# SPort_SBUS.net
KiCad netlist of a schematic drawn in Altium Designer
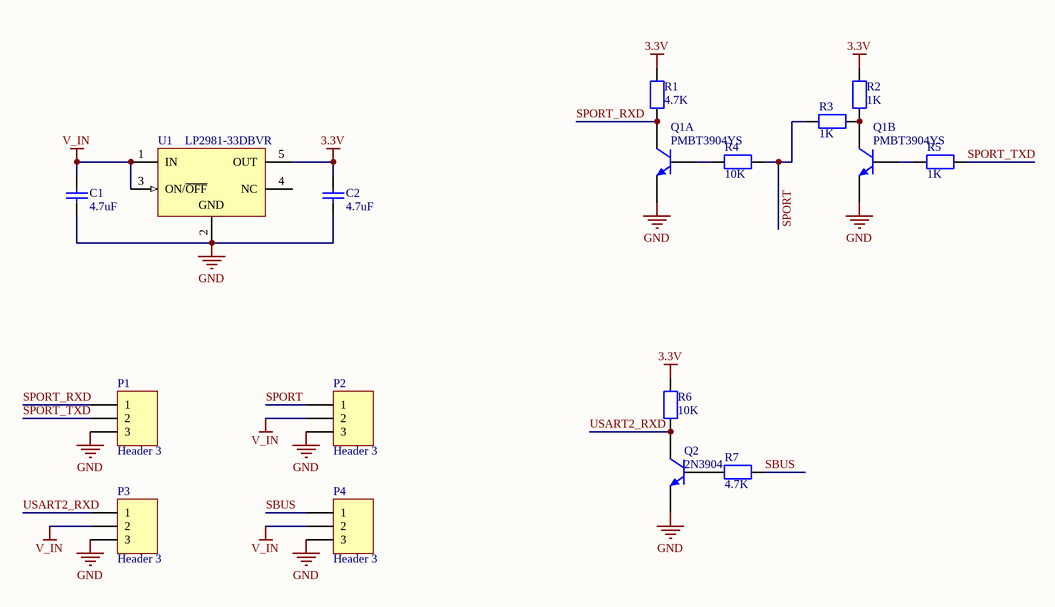
[diagram p0: SPort_SBUS.SchDoc]

(export (version "E")
  (design (tool "Eeschema 10.0.6"))
  (components
    (comp (ref "C1")
      (value "4.7uF")
      (footprint "0603_CAP")
      (fields (field (name "Comment") "Capacitor"))
      (libsource (lib "Passive_comp") (part "Capacitor"))
    )
    (comp (ref "C2")
      (value "4.7uF")
      (footprint "0603_CAP")
      (fields (field (name "Comment") "Capacitor"))
      (libsource (lib "Passive_comp") (part "Capacitor"))
    )
    (comp (ref "P1")
      (value "Header 3")
      (footprint "Header_3")
      (description "Header, 3-Pin")
      (fields (field (name "PUBLISHER") "Altium Limited"))
      (libsource (lib "Misc_connectors") (part "Header 3"))
    )
    (comp (ref "P2")
      (value "Header 3")
      (footprint "Header_3")
      (description "Header, 3-Pin")
      (fields (field (name "PUBLISHER") "Altium Limited"))
      (libsource (lib "Misc_connectors") (part "Header 3"))
    )
    (comp (ref "P3")
      (value "Header 3")
      (footprint "Header_3")
      (description "Header, 3-Pin")
      (fields (field (name "PUBLISHER") "Altium Limited"))
      (libsource (lib "Misc_connectors") (part "Header 3"))
    )
    (comp (ref "P4")
      (value "Header 3")
      (footprint "Header_3")
      (description "Header, 3-Pin")
      (fields (field (name "PUBLISHER") "Altium Limited"))
      (libsource (lib "Misc_connectors") (part "Header 3"))
    )
    (comp (ref "Q1")
      (value "PMBT3904YS")
      (footprint "SOT363 (SC-88)")
      (libsource (lib "Active_comp") (part "PMBT3904YS"))
    )
    (comp (ref "Q2")
      (value "2N3904")
      (footprint "SOT95P240X120-3M")
      (description "NPN General Purpose Amplifier")
      (fields (field (name "PUBLISHER") "Altium Limited"))
      (libsource (lib "Active_comp") (part "2N3904"))
    )
    (comp (ref "R1")
      (value "4.7K")
      (footprint "0603_RES")
      (fields (field (name "Comment") "Resitor"))
      (libsource (lib "") (part "Resitor_3"))
    )
    (comp (ref "R2")
      (value "1K")
      (footprint "0603_RES")
      (fields (field (name "Comment") "Resitor"))
      (libsource (lib "Passive_comp") (part "Resitor"))
    )
    (comp (ref "R3")
      (value "1K")
      (footprint "0603_RES")
      (fields (field (name "Comment") "Resitor"))
      (libsource (lib "") (part "Resitor_1"))
    )
    (comp (ref "R4")
      (value "10K")
      (footprint "0603_RES")
      (fields (field (name "Comment") "Resitor"))
      (libsource (lib "") (part "Resitor_2"))
    )
    (comp (ref "R5")
      (value "1K")
      (footprint "0603_RES")
      (fields (field (name "Comment") "Resitor"))
      (libsource (lib "") (part "Resitor_2"))
    )
    (comp (ref "R6")
      (value "10K")
      (footprint "0603_RES")
      (fields (field (name "Comment") "Resitor"))
      (libsource (lib "Passive_comp") (part "Resitor"))
    )
    (comp (ref "R7")
      (value "4.7K")
      (footprint "0603_RES")
      (fields (field (name "Comment") "Resitor"))
      (libsource (lib "") (part "Resitor_2"))
    )
    (comp (ref "U1")
      (value "LP2981-33DBVR")
      (footprint "MF05A_M")
      (description "Micropower 100 mA Ultra Low-Dropout Regulator, 5-pin SOT-23")
      (fields (field (name "MANUFACTURER") "National Semiconductor"))
      (libsource (lib "Altium Content Vault") (part "CMP-0062-02157-2"))
    )
  )
  (nets
    (net (code "1") (name "/SBUS") (class "Default")
      (node (ref "P4") (pin "1") (pinfunction "1_1") (pintype "passive"))
      (node (ref "R7") (pin "2") (pinfunction "2_2") (pintype "passive"))
    )
    (net (code "2") (name "/SPORT") (class "Default")
      (node (ref "P2") (pin "1") (pinfunction "1_1") (pintype "passive"))
      (node (ref "R3") (pin "2") (pinfunction "2_2") (pintype "passive"))
      (node (ref "R4") (pin "2") (pinfunction "2_2") (pintype "passive"))
    )
    (net (code "3") (name "/SPORT_RXD") (class "Default")
      (node (ref "P1") (pin "1") (pinfunction "1_1") (pintype "passive"))
      (node (ref "Q1") (pin "6") (pinfunction "C_6") (pintype "passive"))
      (node (ref "R1") (pin "2") (pinfunction "2_2") (pintype "passive"))
    )
    (net (code "4") (name "/SPORT_TXD") (class "Default")
      (node (ref "P1") (pin "2") (pinfunction "2_2") (pintype "passive"))
      (node (ref "R5") (pin "2") (pinfunction "2_2") (pintype "passive"))
    )
    (net (code "5") (name "/USART2_RXD") (class "Default")
      (node (ref "P3") (pin "1") (pinfunction "1_1") (pintype "passive"))
      (node (ref "Q2") (pin "3") (pinfunction "C_3") (pintype "passive"))
      (node (ref "R6") (pin "1") (pinfunction "1_1") (pintype "passive"))
    )
    (net (code "6") (name "3.3V") (class "Default")
      (node (ref "C2") (pin "2") (pinfunction "2_2") (pintype "passive"))
      (node (ref "R1") (pin "1") (pinfunction "1_1") (pintype "passive"))
      (node (ref "R2") (pin "2") (pinfunction "2_2") (pintype "passive"))
      (node (ref "R6") (pin "2") (pinfunction "2_2") (pintype "passive"))
      (node (ref "U1") (pin "5") (pinfunction "OUT_5") (pintype "power_in"))
    )
    (net (code "7") (name "GND") (class "Default")
      (node (ref "C1") (pin "1") (pinfunction "1_1") (pintype "passive"))
      (node (ref "C2") (pin "1") (pinfunction "1_1") (pintype "passive"))
      (node (ref "P1") (pin "3") (pinfunction "3_3") (pintype "passive"))
      (node (ref "P2") (pin "3") (pinfunction "3_3") (pintype "passive"))
      (node (ref "P3") (pin "3") (pinfunction "3_3") (pintype "passive"))
      (node (ref "P4") (pin "3") (pinfunction "3_3") (pintype "passive"))
      (node (ref "Q1") (pin "1") (pinfunction "E_1") (pintype "passive"))
      (node (ref "Q1") (pin "4") (pinfunction "E_4") (pintype "passive"))
      (node (ref "Q2") (pin "1") (pinfunction "E_1") (pintype "passive"))
      (node (ref "U1") (pin "2") (pinfunction "GND_2") (pintype "power_in"))
    )
    (net (code "8") (name "Net-(Q1A-B)") (class "Default")
      (node (ref "Q1") (pin "2") (pinfunction "B_2") (pintype "passive"))
      (node (ref "R4") (pin "1") (pinfunction "1_1") (pintype "passive"))
    )
    (net (code "9") (name "Net-(Q1B-B)") (class "Default")
      (node (ref "Q1") (pin "5") (pinfunction "B_5") (pintype "passive"))
      (node (ref "R5") (pin "1") (pinfunction "1_1") (pintype "passive"))
    )
    (net (code "10") (name "Net-(Q1B-C)") (class "Default")
      (node (ref "Q1") (pin "3") (pinfunction "C_3") (pintype "passive"))
      (node (ref "R2") (pin "1") (pinfunction "1_1") (pintype "passive"))
      (node (ref "R3") (pin "1") (pinfunction "1_1") (pintype "passive"))
    )
    (net (code "11") (name "Net-(Q2-B)") (class "Default")
      (node (ref "Q2") (pin "2") (pinfunction "B_2") (pintype "passive"))
      (node (ref "R7") (pin "1") (pinfunction "1_1") (pintype "passive"))
    )
    (net (code "12") (name "V_IN") (class "Default")
      (node (ref "C1") (pin "2") (pinfunction "2_2") (pintype "passive"))
      (node (ref "P2") (pin "2") (pinfunction "2_2") (pintype "passive"))
      (node (ref "P3") (pin "2") (pinfunction "2_2") (pintype "passive"))
      (node (ref "P4") (pin "2") (pinfunction "2_2") (pintype "passive"))
      (node (ref "U1") (pin "1") (pinfunction "IN_1") (pintype "power_in"))
      (node (ref "U1") (pin "3") (pinfunction "ON/~{OFF}_3") (pintype "input"))
    )
    (net (code "13") (name "unconnected-(U1-NC-Pad4)") (class "Default")
      (node (ref "U1") (pin "4") (pinfunction "NC_4") (pintype "passive"))
    )
  )
)
